# Transceiver.net
KiCad netlist of a schematic drawn in Altium Designer
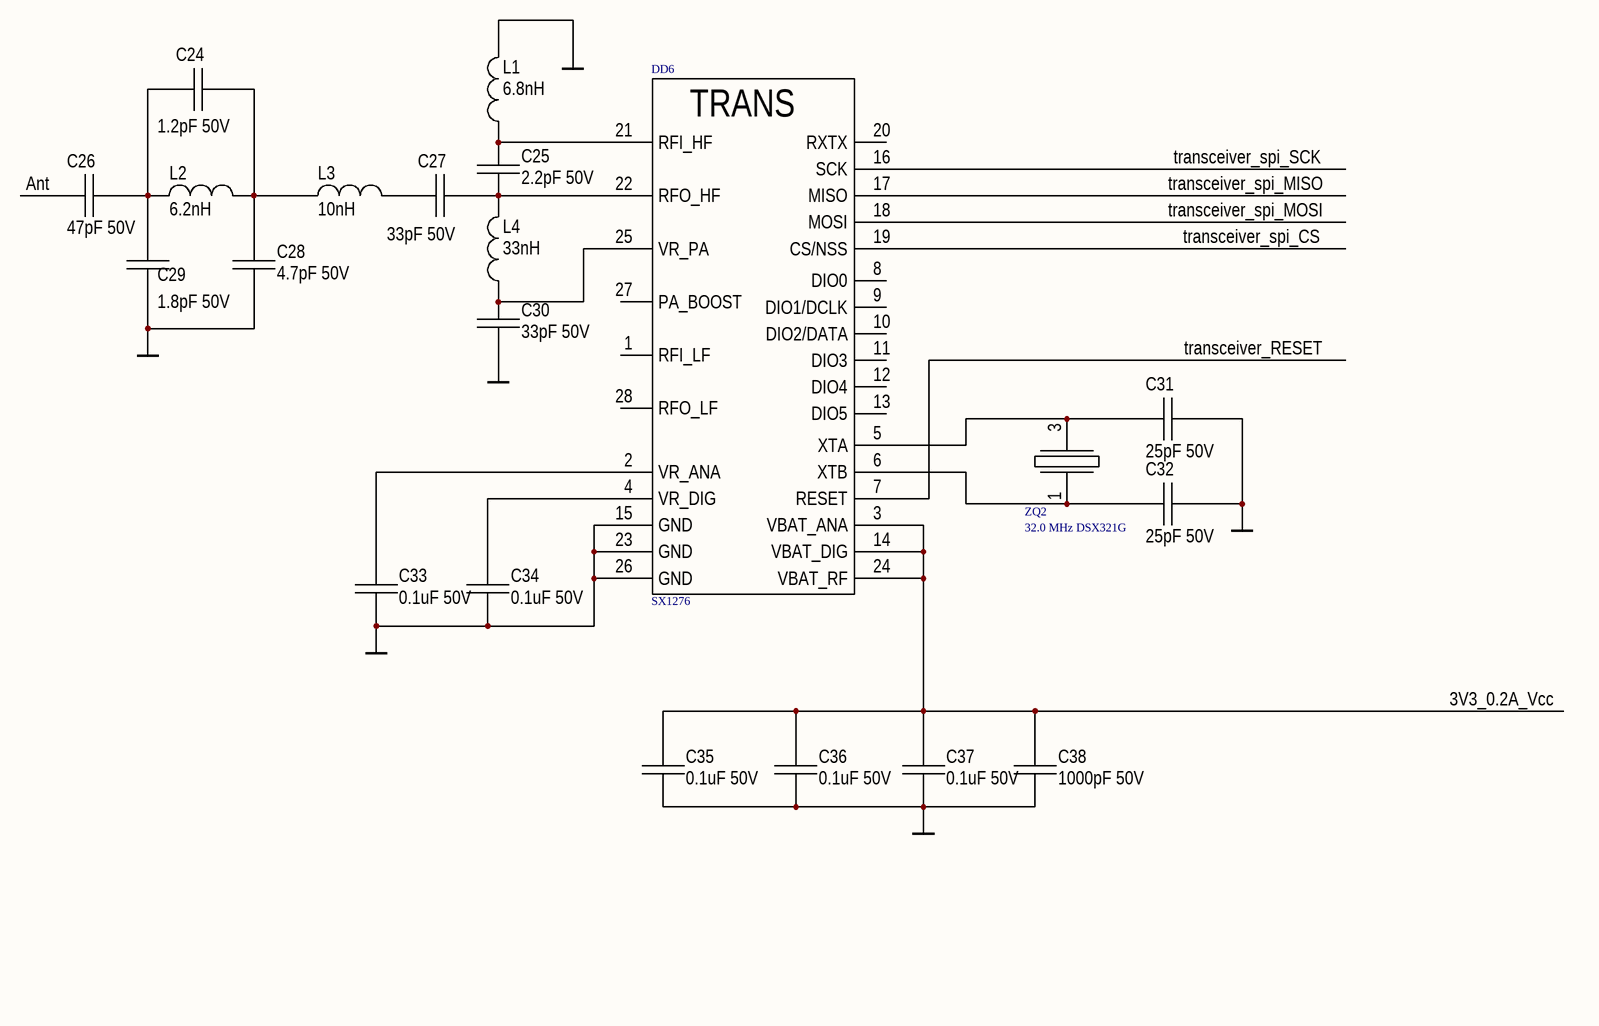
[diagram p0: Transceiver.SchDoc]

(export (version "E")
  (design (tool "Eeschema 10.0.6"))
  (components
    (comp (ref "C24") (value "1.2pF 50V") (footprint "0603_CAP") (libsource (lib "") (part "Cap_np_1")))
    (comp (ref "C25")
      (value "2.2pF 50V")
      (footprint "0603_CAP")
      (libsource (lib "Integrated_Library_tikhovikt") (part "Cap_np"))
    )
    (comp (ref "C26")
      (value "47pF 50V")
      (footprint "0603_CAP")
      (libsource (lib "Integrated_Library_tikhovikt") (part "Cap_np"))
    )
    (comp (ref "C27")
      (value "33pF 50V")
      (footprint "0603_CAP")
      (libsource (lib "Integrated_Library_tikhovikt") (part "Cap_np"))
    )
    (comp (ref "C28")
      (value "4.7pF 50V")
      (footprint "0603_CAP")
      (libsource (lib "Integrated_Library_tikhovikt") (part "Cap_np"))
    )
    (comp (ref "C29")
      (value "1.8pF 50V")
      (footprint "0603_CAP")
      (libsource (lib "Integrated_Library_tikhovikt") (part "Cap_np"))
    )
    (comp (ref "C30")
      (value "33pF 50V")
      (footprint "0603_CAP")
      (libsource (lib "Integrated_Library_tikhovikt") (part "Cap_np"))
    )
    (comp (ref "C31")
      (value "25pF 50V")
      (footprint "0805_CAP")
      (libsource (lib "Integrated_Library_tikhovikt") (part "Cap_np"))
    )
    (comp (ref "C32")
      (value "25pF 50V")
      (footprint "0805_CAP")
      (libsource (lib "Integrated_Library_tikhovikt") (part "Cap_np"))
    )
    (comp (ref "C33")
      (value "0.1uF 50V")
      (footprint "0805_CAP")
      (libsource (lib "Integrated_Library_tikhovikt") (part "Cap_np"))
    )
    (comp (ref "C34")
      (value "0.1uF 50V")
      (footprint "0805_CAP")
      (libsource (lib "Integrated_Library_tikhovikt") (part "Cap_np"))
    )
    (comp (ref "C35")
      (value "0.1uF 50V")
      (footprint "0805_CAP")
      (libsource (lib "Integrated_Library_tikhovikt") (part "Cap_np"))
    )
    (comp (ref "C36")
      (value "0.1uF 50V")
      (footprint "0805_CAP")
      (libsource (lib "Integrated_Library_tikhovikt") (part "Cap_np"))
    )
    (comp (ref "C37")
      (value "0.1uF 50V")
      (footprint "0805_CAP")
      (libsource (lib "Integrated_Library_tikhovikt") (part "Cap_np"))
    )
    (comp (ref "C38")
      (value "1000pF 50V")
      (footprint "0805_CAP")
      (libsource (lib "Integrated_Library_tikhovikt") (part "Cap_np"))
    )
    (comp (ref "DD6")
      (value "SX1276")
      (footprint "qfn28")
      (libsource (lib "Integrated_Library_tikhovikt") (part "SX1276"))
    )
    (comp (ref "L1")
      (value "6.8nH")
      (footprint "0603_ind")
      (libsource (lib "Integrated_Library_tikhovikt") (part "Inductor"))
    )
    (comp (ref "L2")
      (value "6.2nH")
      (footprint "0603_ind")
      (libsource (lib "Integrated_Library_tikhovikt") (part "Inductor"))
    )
    (comp (ref "L3")
      (value "10nH")
      (footprint "0603_ind")
      (libsource (lib "Integrated_Library_tikhovikt") (part "Inductor"))
    )
    (comp (ref "L4")
      (value "33nH")
      (footprint "0603_ind")
      (libsource (lib "Integrated_Library_tikhovikt") (part "Inductor"))
    )
    (comp (ref "ZQ2")
      (value "32.0 MHz DSX321G")
      (footprint "gtxo-93")
      (libsource (lib "Integrated_Library_tikhovikt") (part "Cristall"))
    )
  )
  (nets
    (net (code "1") (name "/3V3_0.2A_Vcc") (class "Default")
      (node (ref "C35") (pin "1") (pinfunction "1_1") (pintype "passive"))
      (node (ref "C36") (pin "1") (pinfunction "1_1") (pintype "passive"))
      (node (ref "C37") (pin "1") (pinfunction "1_1") (pintype "passive"))
      (node (ref "C38") (pin "1") (pinfunction "1_1") (pintype "passive"))
      (node (ref "DD6") (pin "14") (pinfunction "VBAT_DIG_14") (pintype "passive"))
      (node (ref "DD6") (pin "24") (pinfunction "VBAT_RF_24") (pintype "passive"))
      (node (ref "DD6") (pin "3") (pinfunction "VBAT_ANA_3") (pintype "passive"))
    )
    (net (code "2") (name "/Ant") (class "Default")
      (node (ref "C26") (pin "2") (pinfunction "2_2") (pintype "passive"))
    )
    (net (code "3") (name "/transceiver_RESET") (class "Default")
      (node (ref "DD6") (pin "7") (pinfunction "RESET_7") (pintype "passive"))
    )
    (net (code "4") (name "/transceiver_spi_CS") (class "Default")
      (node (ref "DD6") (pin "19") (pinfunction "CS/NSS_19") (pintype "passive"))
    )
    (net (code "5") (name "/transceiver_spi_MISO") (class "Default")
      (node (ref "DD6") (pin "17") (pinfunction "MISO_17") (pintype "passive"))
    )
    (net (code "6") (name "/transceiver_spi_MOSI") (class "Default")
      (node (ref "DD6") (pin "18") (pinfunction "MOSI_18") (pintype "passive"))
    )
    (net (code "7") (name "/transceiver_spi_SCK") (class "Default")
      (node (ref "DD6") (pin "16") (pinfunction "SCK_16") (pintype "passive"))
    )
    (net (code "8") (name "GND") (class "Default")
      (node (ref "C28") (pin "2") (pinfunction "2_2") (pintype "passive"))
      (node (ref "C29") (pin "1") (pinfunction "1_1") (pintype "passive"))
      (node (ref "C30") (pin "2") (pinfunction "2_2") (pintype "passive"))
      (node (ref "C31") (pin "2") (pinfunction "2_2") (pintype "passive"))
      (node (ref "C32") (pin "2") (pinfunction "2_2") (pintype "passive"))
      (node (ref "C33") (pin "1") (pinfunction "1_1") (pintype "passive"))
      (node (ref "C34") (pin "2") (pinfunction "2_2") (pintype "passive"))
      (node (ref "C35") (pin "2") (pinfunction "2_2") (pintype "passive"))
      (node (ref "C36") (pin "2") (pinfunction "2_2") (pintype "passive"))
      (node (ref "C37") (pin "2") (pinfunction "2_2") (pintype "passive"))
      (node (ref "C38") (pin "2") (pinfunction "2_2") (pintype "passive"))
      (node (ref "DD6") (pin "15") (pinfunction "GND_15") (pintype "passive"))
      (node (ref "DD6") (pin "23") (pinfunction "GND_23") (pintype "passive"))
      (node (ref "DD6") (pin "26") (pinfunction "GND_26") (pintype "passive"))
      (node (ref "L1") (pin "2") (pinfunction "2_2") (pintype "passive"))
    )
    (net (code "9") (name "Net-(C24-Pad1)") (class "Default")
      (node (ref "C24") (pin "1") (pinfunction "1_1") (pintype "passive"))
      (node (ref "C26") (pin "1") (pinfunction "1_1") (pintype "passive"))
      (node (ref "C29") (pin "2") (pinfunction "2_2") (pintype "passive"))
      (node (ref "L2") (pin "1") (pinfunction "1_1") (pintype "passive"))
    )
    (net (code "10") (name "Net-(C24-Pad2)") (class "Default")
      (node (ref "C24") (pin "2") (pinfunction "2_2") (pintype "passive"))
      (node (ref "C28") (pin "1") (pinfunction "1_1") (pintype "passive"))
      (node (ref "L2") (pin "2") (pinfunction "2_2") (pintype "passive"))
      (node (ref "L3") (pin "1") (pinfunction "1_1") (pintype "passive"))
    )
    (net (code "11") (name "Net-(C27-Pad2)") (class "Default")
      (node (ref "C27") (pin "2") (pinfunction "2_2") (pintype "passive"))
      (node (ref "L3") (pin "2") (pinfunction "2_2") (pintype "passive"))
    )
    (net (code "12") (name "Net-(DD6-RFI_HF)") (class "Default")
      (node (ref "C25") (pin "2") (pinfunction "2_2") (pintype "passive"))
      (node (ref "DD6") (pin "21") (pinfunction "RFI_HF_21") (pintype "passive"))
      (node (ref "L1") (pin "1") (pinfunction "1_1") (pintype "passive"))
    )
    (net (code "13") (name "Net-(DD6-RFO_HF)") (class "Default")
      (node (ref "C25") (pin "1") (pinfunction "1_1") (pintype "passive"))
      (node (ref "C27") (pin "1") (pinfunction "1_1") (pintype "passive"))
      (node (ref "DD6") (pin "22") (pinfunction "RFO_HF_22") (pintype "passive"))
      (node (ref "L4") (pin "2") (pinfunction "2_2") (pintype "passive"))
    )
    (net (code "14") (name "Net-(DD6-VR_ANA)") (class "Default")
      (node (ref "C33") (pin "2") (pinfunction "2_2") (pintype "passive"))
      (node (ref "DD6") (pin "2") (pinfunction "VR_ANA_2") (pintype "passive"))
    )
    (net (code "15") (name "Net-(DD6-VR_DIG)") (class "Default")
      (node (ref "C34") (pin "1") (pinfunction "1_1") (pintype "passive"))
      (node (ref "DD6") (pin "4") (pinfunction "VR_DIG_4") (pintype "passive"))
    )
    (net (code "16") (name "Net-(DD6-VR_PA)") (class "Default")
      (node (ref "C30") (pin "1") (pinfunction "1_1") (pintype "passive"))
      (node (ref "DD6") (pin "25") (pinfunction "VR_PA_25") (pintype "passive"))
      (node (ref "L4") (pin "1") (pinfunction "1_1") (pintype "passive"))
    )
    (net (code "17") (name "Net-(DD6-XTA)") (class "Default")
      (node (ref "C31") (pin "1") (pinfunction "1_1") (pintype "passive"))
      (node (ref "DD6") (pin "5") (pinfunction "XTA_5") (pintype "passive"))
      (node (ref "ZQ2") (pin "3") (pinfunction "3_3") (pintype "passive"))
    )
    (net (code "18") (name "Net-(DD6-XTB)") (class "Default")
      (node (ref "C32") (pin "1") (pinfunction "1_1") (pintype "passive"))
      (node (ref "DD6") (pin "6") (pinfunction "XTB_6") (pintype "passive"))
      (node (ref "ZQ2") (pin "1") (pinfunction "1_1") (pintype "passive"))
    )
    (net (code "19") (name "unconnected-(DD6-DIO0-Pad8)") (class "Default")
      (node (ref "DD6") (pin "8") (pinfunction "DIO0_8") (pintype "passive"))
    )
    (net (code "20") (name "unconnected-(DD6-DIO1{slash}DCLK-Pad9)") (class "Default")
      (node (ref "DD6") (pin "9") (pinfunction "DIO1/DCLK_9") (pintype "passive"))
    )
    (net (code "21") (name "unconnected-(DD6-DIO2{slash}DATA-Pad10)") (class "Default")
      (node (ref "DD6") (pin "10") (pinfunction "DIO2/DATA_10") (pintype "passive"))
    )
    (net (code "22") (name "unconnected-(DD6-DIO3-Pad11)") (class "Default")
      (node (ref "DD6") (pin "11") (pinfunction "DIO3_11") (pintype "passive"))
    )
    (net (code "23") (name "unconnected-(DD6-DIO4-Pad12)") (class "Default")
      (node (ref "DD6") (pin "12") (pinfunction "DIO4_12") (pintype "passive"))
    )
    (net (code "24") (name "unconnected-(DD6-DIO5-Pad13)") (class "Default")
      (node (ref "DD6") (pin "13") (pinfunction "DIO5_13") (pintype "passive"))
    )
    (net (code "25") (name "unconnected-(DD6-PA_BOOST-Pad27)") (class "Default")
      (node (ref "DD6") (pin "27") (pinfunction "PA_BOOST_27") (pintype "passive"))
    )
    (net (code "26") (name "unconnected-(DD6-RFI_LF-Pad1)") (class "Default")
      (node (ref "DD6") (pin "1") (pinfunction "RFI_LF_1") (pintype "passive"))
    )
    (net (code "27") (name "unconnected-(DD6-RFO_LF-Pad28)") (class "Default")
      (node (ref "DD6") (pin "28") (pinfunction "RFO_LF_28") (pintype "passive"))
    )
    (net (code "28") (name "unconnected-(DD6-RXTX-Pad20)") (class "Default")
      (node (ref "DD6") (pin "20") (pinfunction "RXTX_20") (pintype "passive"))
    )
  )
)
